# DebugPowerSupplyBoard.net
KiCad netlist of a schematic drawn in EAGLE
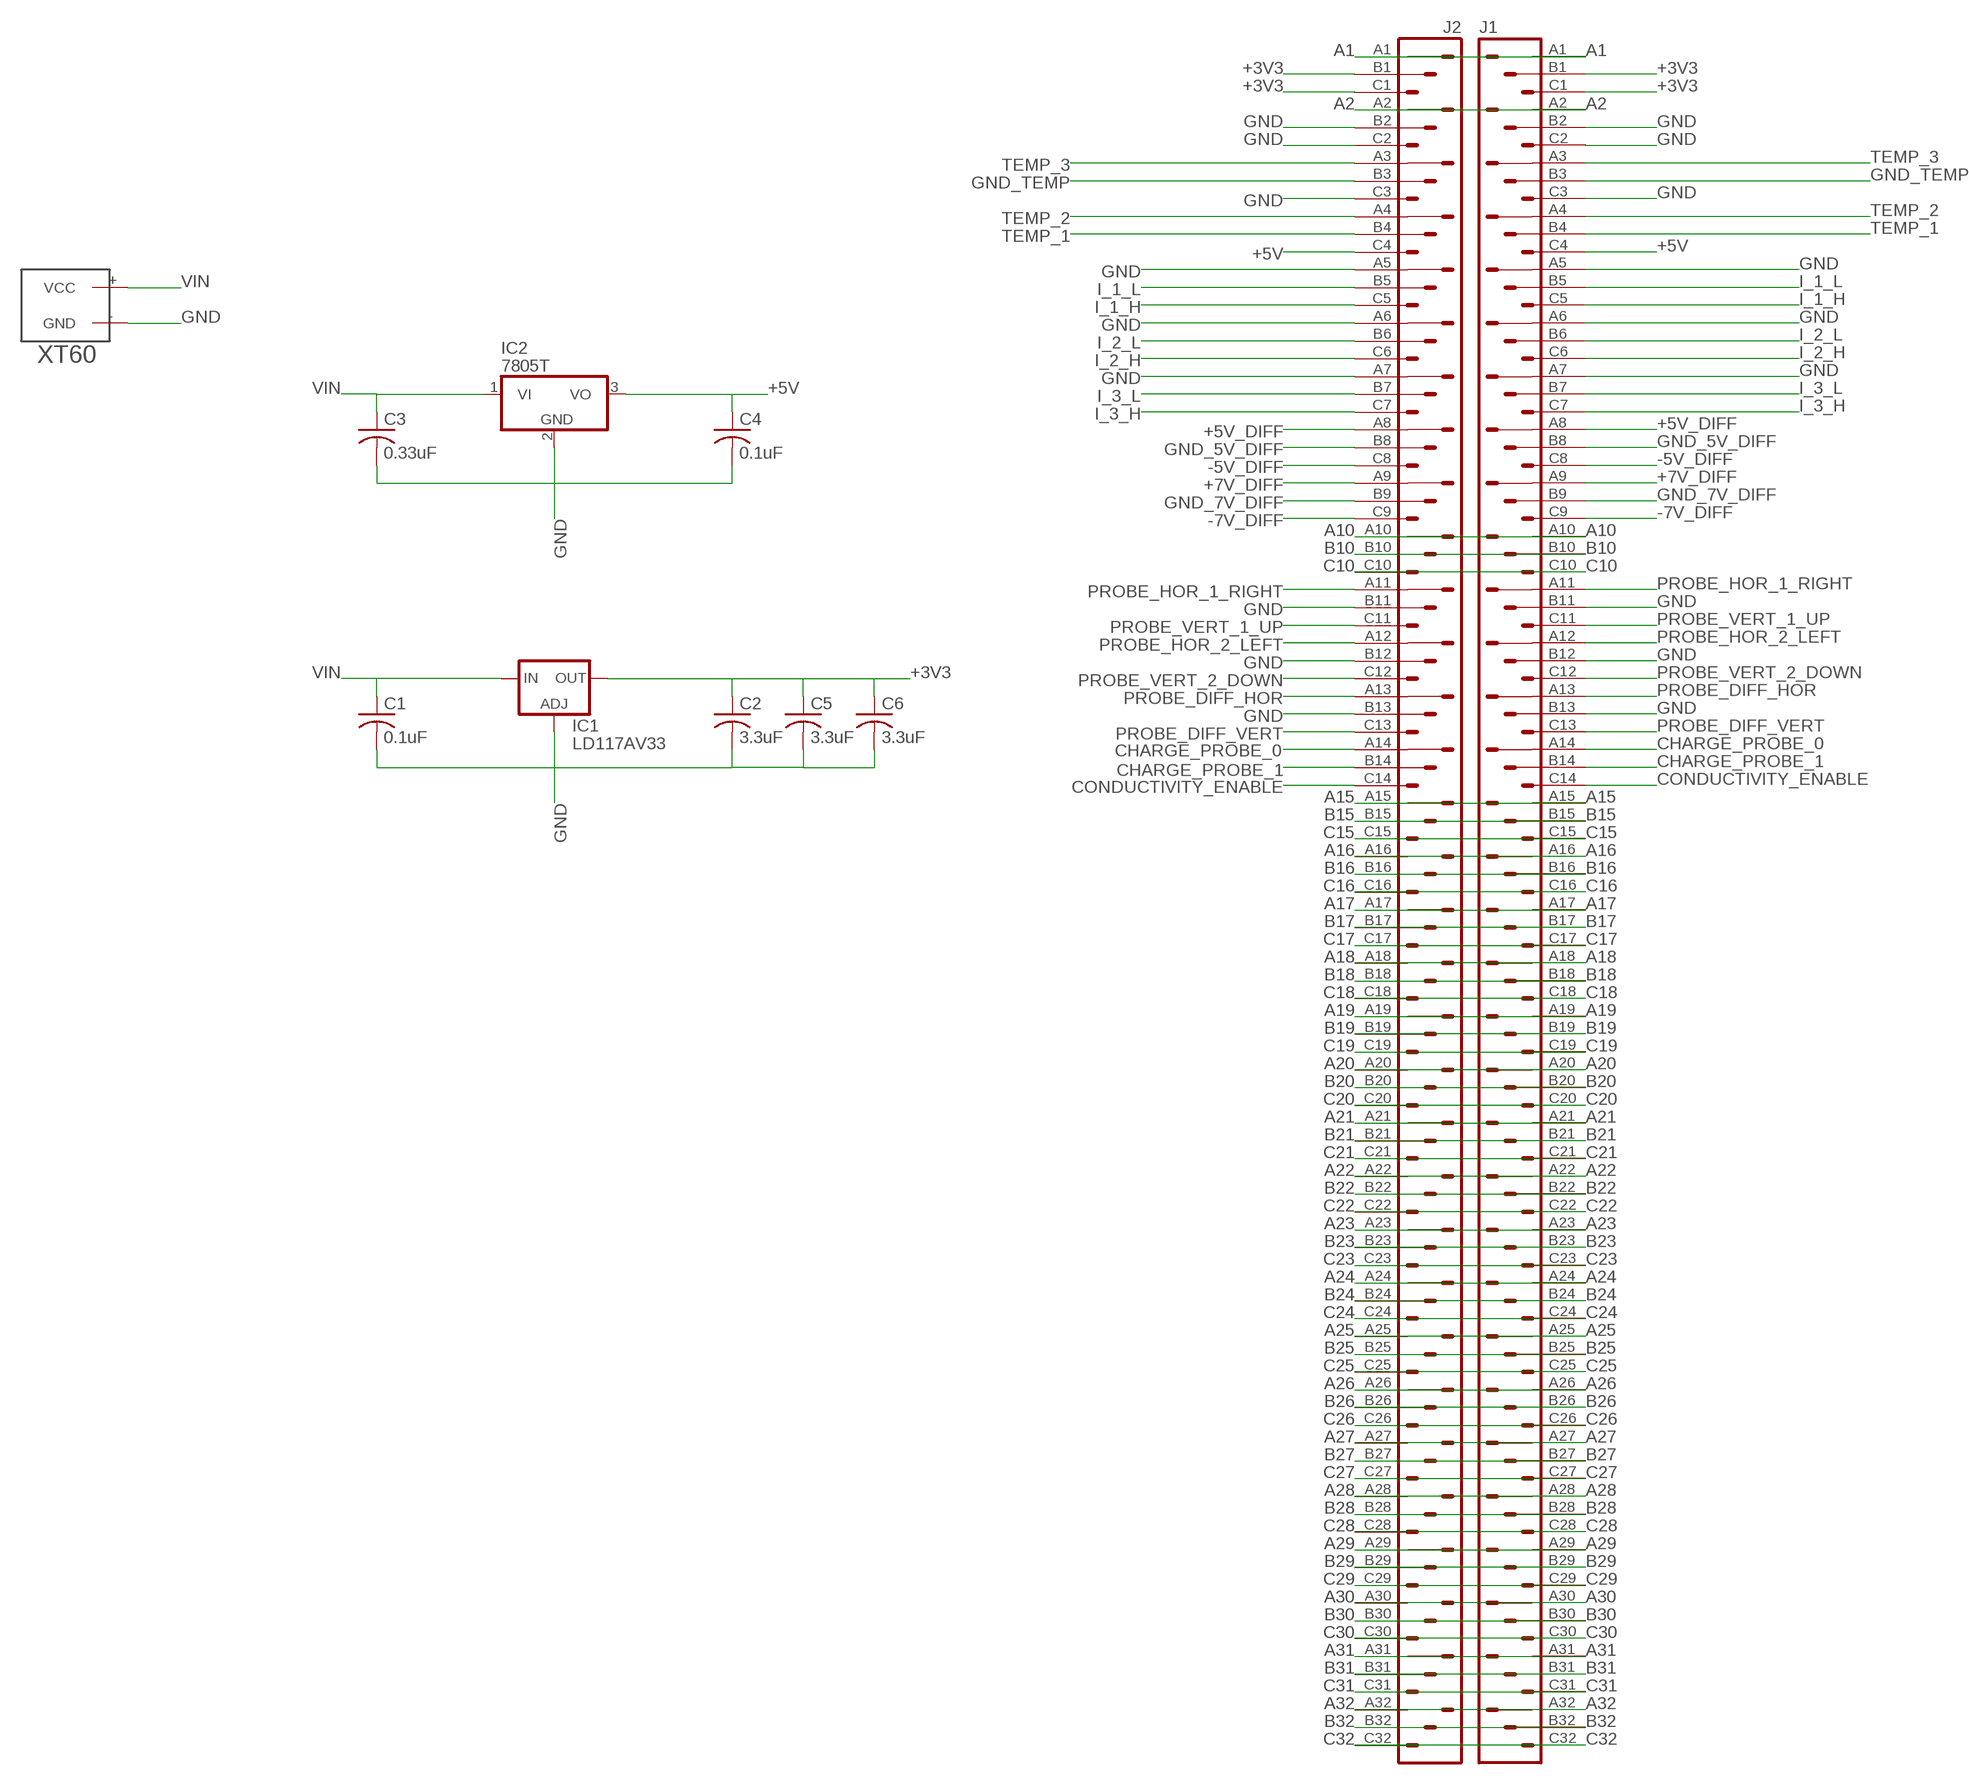
[diagram p0: schematic, sheet 1]

(export (version "E")
  (design (tool "Eeschema 10.0.6"))
  (components
    (comp (ref "C1")
      (value "0.1uF")
      (footprint "eagle-import:C050-025X075")
      (libsource (lib "eagle-import") (part "C-US050-025X075"))
    )
    (comp (ref "C2")
      (value "3.3uF")
      (footprint "eagle-import:C050-055X075")
      (libsource (lib "eagle-import") (part "C-US050-055X075"))
    )
    (comp (ref "C3")
      (value "0.33uF")
      (footprint "eagle-import:C050-035X075")
      (libsource (lib "eagle-import") (part "C-US050-035X075"))
    )
    (comp (ref "C4")
      (value "0.1uF")
      (footprint "eagle-import:C050-025X075")
      (libsource (lib "eagle-import") (part "C-US050-025X075"))
    )
    (comp (ref "C5")
      (value "3.3uF")
      (footprint "eagle-import:C050-055X075")
      (libsource (lib "eagle-import") (part "C-US050-055X075"))
    )
    (comp (ref "C6")
      (value "3.3uF")
      (footprint "eagle-import:C050-055X075")
      (libsource (lib "eagle-import") (part "C-US050-055X075"))
    )
    (comp (ref "IC1")
      (value "LD117AV33")
      (footprint "eagle-import:TO220L1")
      (libsource (lib "eagle-import") (part "LD117A?V33"))
    )
    (comp (ref "IC2")
      (value "7805T")
      (footprint "eagle-import:TO220H")
      (libsource (lib "eagle-import") (part "78T05"))
    )
    (comp (ref "J1")
      (value "VG96KB")
      (footprint "eagle-import:VG96KB")
      (libsource (lib "eagle-import") (part "CustomEuroCard_VG96KB"))
    )
    (comp (ref "J2")
      (value "VG96KB")
      (footprint "eagle-import:VG96KB")
      (libsource (lib "eagle-import") (part "VG96KB"))
    )
    (comp (ref "U$6")
      (value "XT60")
      (footprint "eagle-import:XT60")
      (libsource (lib "eagle-import") (part "XT60"))
    )
  )
  (nets
    (net (code "1") (name "/+3V3") (class "Default")
      (node (ref "C2") (pin "1") (pinfunction "1_1") (pintype "passive"))
      (node (ref "C5") (pin "1") (pinfunction "1_1") (pintype "passive"))
      (node (ref "C6") (pin "1") (pinfunction "1_1") (pintype "passive"))
      (node (ref "IC1") (pin "2") (pinfunction "OUT_2") (pintype "passive"))
      (node (ref "J1") (pin "B1") (pinfunction "B1_B1") (pintype "passive"))
      (node (ref "J1") (pin "C1") (pinfunction "C1_C1") (pintype "passive"))
      (node (ref "J2") (pin "B1") (pinfunction "B1_B1") (pintype "passive"))
      (node (ref "J2") (pin "C1") (pinfunction "C1_C1") (pintype "passive"))
    )
    (net (code "2") (name "/+5V") (class "Default")
      (node (ref "C4") (pin "1") (pinfunction "1_1") (pintype "passive"))
      (node (ref "IC2") (pin "3") (pinfunction "VO_3") (pintype "passive"))
      (node (ref "J1") (pin "C4") (pinfunction "C4_C4") (pintype "passive"))
      (node (ref "J2") (pin "C4") (pinfunction "C4_C4") (pintype "passive"))
    )
    (net (code "3") (name "/+5V_DIFF") (class "Default")
      (node (ref "J1") (pin "A8") (pinfunction "A8_A8") (pintype "passive"))
      (node (ref "J2") (pin "A8") (pinfunction "A8_A8") (pintype "passive"))
    )
    (net (code "4") (name "/+7V_DIFF") (class "Default")
      (node (ref "J1") (pin "A9") (pinfunction "A9_A9") (pintype "passive"))
      (node (ref "J2") (pin "A9") (pinfunction "A9_A9") (pintype "passive"))
    )
    (net (code "5") (name "/-5V_DIFF") (class "Default")
      (node (ref "J1") (pin "C8") (pinfunction "C8_C8") (pintype "passive"))
      (node (ref "J2") (pin "C8") (pinfunction "C8_C8") (pintype "passive"))
    )
    (net (code "6") (name "/-7V_DIFF") (class "Default")
      (node (ref "J1") (pin "C9") (pinfunction "C9_C9") (pintype "passive"))
      (node (ref "J2") (pin "C9") (pinfunction "C9_C9") (pintype "passive"))
    )
    (net (code "7") (name "/A1") (class "Default")
      (node (ref "J1") (pin "A1") (pinfunction "A1_A1") (pintype "passive"))
      (node (ref "J2") (pin "A1") (pinfunction "A1_A1") (pintype "passive"))
    )
    (net (code "8") (name "/A2") (class "Default")
      (node (ref "J1") (pin "A2") (pinfunction "A2_A2") (pintype "passive"))
      (node (ref "J2") (pin "A2") (pinfunction "A2_A2") (pintype "passive"))
    )
    (net (code "9") (name "/A10") (class "Default")
      (node (ref "J1") (pin "A10") (pinfunction "A10_A10") (pintype "passive"))
      (node (ref "J2") (pin "A10") (pinfunction "A10_A10") (pintype "passive"))
    )
    (net (code "10") (name "/A15") (class "Default")
      (node (ref "J1") (pin "A15") (pinfunction "A15_A15") (pintype "passive"))
      (node (ref "J2") (pin "A15") (pinfunction "A15_A15") (pintype "passive"))
    )
    (net (code "11") (name "/A16") (class "Default")
      (node (ref "J1") (pin "A16") (pinfunction "A16_A16") (pintype "passive"))
      (node (ref "J2") (pin "A16") (pinfunction "A16_A16") (pintype "passive"))
    )
    (net (code "12") (name "/A17") (class "Default")
      (node (ref "J1") (pin "A17") (pinfunction "A17_A17") (pintype "passive"))
      (node (ref "J2") (pin "A17") (pinfunction "A17_A17") (pintype "passive"))
    )
    (net (code "13") (name "/A18") (class "Default")
      (node (ref "J1") (pin "A18") (pinfunction "A18_A18") (pintype "passive"))
      (node (ref "J2") (pin "A18") (pinfunction "A18_A18") (pintype "passive"))
    )
    (net (code "14") (name "/A19") (class "Default")
      (node (ref "J1") (pin "A19") (pinfunction "A19_A19") (pintype "passive"))
      (node (ref "J2") (pin "A19") (pinfunction "A19_A19") (pintype "passive"))
    )
    (net (code "15") (name "/A20") (class "Default")
      (node (ref "J1") (pin "A20") (pinfunction "A20_A20") (pintype "passive"))
      (node (ref "J2") (pin "A20") (pinfunction "A20_A20") (pintype "passive"))
    )
    (net (code "16") (name "/A21") (class "Default")
      (node (ref "J1") (pin "A21") (pinfunction "A21_A21") (pintype "passive"))
      (node (ref "J2") (pin "A21") (pinfunction "A21_A21") (pintype "passive"))
    )
    (net (code "17") (name "/A22") (class "Default")
      (node (ref "J1") (pin "A22") (pinfunction "A22_A22") (pintype "passive"))
      (node (ref "J2") (pin "A22") (pinfunction "A22_A22") (pintype "passive"))
    )
    (net (code "18") (name "/A23") (class "Default")
      (node (ref "J1") (pin "A23") (pinfunction "A23_A23") (pintype "passive"))
      (node (ref "J2") (pin "A23") (pinfunction "A23_A23") (pintype "passive"))
    )
    (net (code "19") (name "/A24") (class "Default")
      (node (ref "J1") (pin "A24") (pinfunction "A24_A24") (pintype "passive"))
      (node (ref "J2") (pin "A24") (pinfunction "A24_A24") (pintype "passive"))
    )
    (net (code "20") (name "/A25") (class "Default")
      (node (ref "J1") (pin "A25") (pinfunction "A25_A25") (pintype "passive"))
      (node (ref "J2") (pin "A25") (pinfunction "A25_A25") (pintype "passive"))
    )
    (net (code "21") (name "/A26") (class "Default")
      (node (ref "J1") (pin "A26") (pinfunction "A26_A26") (pintype "passive"))
      (node (ref "J2") (pin "A26") (pinfunction "A26_A26") (pintype "passive"))
    )
    (net (code "22") (name "/A27") (class "Default")
      (node (ref "J1") (pin "A27") (pinfunction "A27_A27") (pintype "passive"))
      (node (ref "J2") (pin "A27") (pinfunction "A27_A27") (pintype "passive"))
    )
    (net (code "23") (name "/A28") (class "Default")
      (node (ref "J1") (pin "A28") (pinfunction "A28_A28") (pintype "passive"))
      (node (ref "J2") (pin "A28") (pinfunction "A28_A28") (pintype "passive"))
    )
    (net (code "24") (name "/A29") (class "Default")
      (node (ref "J1") (pin "A29") (pinfunction "A29_A29") (pintype "passive"))
      (node (ref "J2") (pin "A29") (pinfunction "A29_A29") (pintype "passive"))
    )
    (net (code "25") (name "/A30") (class "Default")
      (node (ref "J1") (pin "A30") (pinfunction "A30_A30") (pintype "passive"))
      (node (ref "J2") (pin "A30") (pinfunction "A30_A30") (pintype "passive"))
    )
    (net (code "26") (name "/A31") (class "Default")
      (node (ref "J1") (pin "A31") (pinfunction "A31_A31") (pintype "passive"))
      (node (ref "J2") (pin "A31") (pinfunction "A31_A31") (pintype "passive"))
    )
    (net (code "27") (name "/A32") (class "Default")
      (node (ref "J1") (pin "A32") (pinfunction "A32_A32") (pintype "passive"))
      (node (ref "J2") (pin "A32") (pinfunction "A32_A32") (pintype "passive"))
    )
    (net (code "28") (name "/B10") (class "Default")
      (node (ref "J1") (pin "B10") (pinfunction "B10_B10") (pintype "passive"))
      (node (ref "J2") (pin "B10") (pinfunction "B10_B10") (pintype "passive"))
    )
    (net (code "29") (name "/B15") (class "Default")
      (node (ref "J1") (pin "B15") (pinfunction "B15_B15") (pintype "passive"))
      (node (ref "J2") (pin "B15") (pinfunction "B15_B15") (pintype "passive"))
    )
    (net (code "30") (name "/B16") (class "Default")
      (node (ref "J1") (pin "B16") (pinfunction "B16_B16") (pintype "passive"))
      (node (ref "J2") (pin "B16") (pinfunction "B16_B16") (pintype "passive"))
    )
    (net (code "31") (name "/B17") (class "Default")
      (node (ref "J1") (pin "B17") (pinfunction "B17_B17") (pintype "passive"))
      (node (ref "J2") (pin "B17") (pinfunction "B17_B17") (pintype "passive"))
    )
    (net (code "32") (name "/B18") (class "Default")
      (node (ref "J1") (pin "B18") (pinfunction "B18_B18") (pintype "passive"))
      (node (ref "J2") (pin "B18") (pinfunction "B18_B18") (pintype "passive"))
    )
    (net (code "33") (name "/B19") (class "Default")
      (node (ref "J1") (pin "B19") (pinfunction "B19_B19") (pintype "passive"))
      (node (ref "J2") (pin "B19") (pinfunction "B19_B19") (pintype "passive"))
    )
    (net (code "34") (name "/B20") (class "Default")
      (node (ref "J1") (pin "B20") (pinfunction "B20_B20") (pintype "passive"))
      (node (ref "J2") (pin "B20") (pinfunction "B20_B20") (pintype "passive"))
    )
    (net (code "35") (name "/B21") (class "Default")
      (node (ref "J1") (pin "B21") (pinfunction "B21_B21") (pintype "passive"))
      (node (ref "J2") (pin "B21") (pinfunction "B21_B21") (pintype "passive"))
    )
    (net (code "36") (name "/B22") (class "Default")
      (node (ref "J1") (pin "B22") (pinfunction "B22_B22") (pintype "passive"))
      (node (ref "J2") (pin "B22") (pinfunction "B22_B22") (pintype "passive"))
    )
    (net (code "37") (name "/B23") (class "Default")
      (node (ref "J1") (pin "B23") (pinfunction "B23_B23") (pintype "passive"))
      (node (ref "J2") (pin "B23") (pinfunction "B23_B23") (pintype "passive"))
    )
    (net (code "38") (name "/B24") (class "Default")
      (node (ref "J1") (pin "B24") (pinfunction "B24_B24") (pintype "passive"))
      (node (ref "J2") (pin "B24") (pinfunction "B24_B24") (pintype "passive"))
    )
    (net (code "39") (name "/B25") (class "Default")
      (node (ref "J1") (pin "B25") (pinfunction "B25_B25") (pintype "passive"))
      (node (ref "J2") (pin "B25") (pinfunction "B25_B25") (pintype "passive"))
    )
    (net (code "40") (name "/B26") (class "Default")
      (node (ref "J1") (pin "B26") (pinfunction "B26_B26") (pintype "passive"))
      (node (ref "J2") (pin "B26") (pinfunction "B26_B26") (pintype "passive"))
    )
    (net (code "41") (name "/B27") (class "Default")
      (node (ref "J1") (pin "B27") (pinfunction "B27_B27") (pintype "passive"))
      (node (ref "J2") (pin "B27") (pinfunction "B27_B27") (pintype "passive"))
    )
    (net (code "42") (name "/B28") (class "Default")
      (node (ref "J1") (pin "B28") (pinfunction "B28_B28") (pintype "passive"))
      (node (ref "J2") (pin "B28") (pinfunction "B28_B28") (pintype "passive"))
    )
    (net (code "43") (name "/B29") (class "Default")
      (node (ref "J1") (pin "B29") (pinfunction "B29_B29") (pintype "passive"))
      (node (ref "J2") (pin "B29") (pinfunction "B29_B29") (pintype "passive"))
    )
    (net (code "44") (name "/B30") (class "Default")
      (node (ref "J1") (pin "B30") (pinfunction "B30_B30") (pintype "passive"))
      (node (ref "J2") (pin "B30") (pinfunction "B30_B30") (pintype "passive"))
    )
    (net (code "45") (name "/B31") (class "Default")
      (node (ref "J1") (pin "B31") (pinfunction "B31_B31") (pintype "passive"))
      (node (ref "J2") (pin "B31") (pinfunction "B31_B31") (pintype "passive"))
    )
    (net (code "46") (name "/B32") (class "Default")
      (node (ref "J1") (pin "B32") (pinfunction "B32_B32") (pintype "passive"))
      (node (ref "J2") (pin "B32") (pinfunction "B32_B32") (pintype "passive"))
    )
    (net (code "47") (name "/C10") (class "Default")
      (node (ref "J1") (pin "C10") (pinfunction "C10_C10") (pintype "passive"))
      (node (ref "J2") (pin "C10") (pinfunction "C10_C10") (pintype "passive"))
    )
    (net (code "48") (name "/C15") (class "Default")
      (node (ref "J1") (pin "C15") (pinfunction "C15_C15") (pintype "passive"))
      (node (ref "J2") (pin "C15") (pinfunction "C15_C15") (pintype "passive"))
    )
    (net (code "49") (name "/C16") (class "Default")
      (node (ref "J1") (pin "C16") (pinfunction "C16_C16") (pintype "passive"))
      (node (ref "J2") (pin "C16") (pinfunction "C16_C16") (pintype "passive"))
    )
    (net (code "50") (name "/C17") (class "Default")
      (node (ref "J1") (pin "C17") (pinfunction "C17_C17") (pintype "passive"))
      (node (ref "J2") (pin "C17") (pinfunction "C17_C17") (pintype "passive"))
    )
    (net (code "51") (name "/C18") (class "Default")
      (node (ref "J1") (pin "C18") (pinfunction "C18_C18") (pintype "passive"))
      (node (ref "J2") (pin "C18") (pinfunction "C18_C18") (pintype "passive"))
    )
    (net (code "52") (name "/C19") (class "Default")
      (node (ref "J1") (pin "C19") (pinfunction "C19_C19") (pintype "passive"))
      (node (ref "J2") (pin "C19") (pinfunction "C19_C19") (pintype "passive"))
    )
    (net (code "53") (name "/C20") (class "Default")
      (node (ref "J1") (pin "C20") (pinfunction "C20_C20") (pintype "passive"))
      (node (ref "J2") (pin "C20") (pinfunction "C20_C20") (pintype "passive"))
    )
    (net (code "54") (name "/C21") (class "Default")
      (node (ref "J1") (pin "C21") (pinfunction "C21_C21") (pintype "passive"))
      (node (ref "J2") (pin "C21") (pinfunction "C21_C21") (pintype "passive"))
    )
    (net (code "55") (name "/C22") (class "Default")
      (node (ref "J1") (pin "C22") (pinfunction "C22_C22") (pintype "passive"))
      (node (ref "J2") (pin "C22") (pinfunction "C22_C22") (pintype "passive"))
    )
    (net (code "56") (name "/C23") (class "Default")
      (node (ref "J1") (pin "C23") (pinfunction "C23_C23") (pintype "passive"))
      (node (ref "J2") (pin "C23") (pinfunction "C23_C23") (pintype "passive"))
    )
    (net (code "57") (name "/C24") (class "Default")
      (node (ref "J1") (pin "C24") (pinfunction "C24_C24") (pintype "passive"))
      (node (ref "J2") (pin "C24") (pinfunction "C24_C24") (pintype "passive"))
    )
    (net (code "58") (name "/C25") (class "Default")
      (node (ref "J1") (pin "C25") (pinfunction "C25_C25") (pintype "passive"))
      (node (ref "J2") (pin "C25") (pinfunction "C25_C25") (pintype "passive"))
    )
    (net (code "59") (name "/C26") (class "Default")
      (node (ref "J1") (pin "C26") (pinfunction "C26_C26") (pintype "passive"))
      (node (ref "J2") (pin "C26") (pinfunction "C26_C26") (pintype "passive"))
    )
    (net (code "60") (name "/C27") (class "Default")
      (node (ref "J1") (pin "C27") (pinfunction "C27_C27") (pintype "passive"))
      (node (ref "J2") (pin "C27") (pinfunction "C27_C27") (pintype "passive"))
    )
    (net (code "61") (name "/C28") (class "Default")
      (node (ref "J1") (pin "C28") (pinfunction "C28_C28") (pintype "passive"))
      (node (ref "J2") (pin "C28") (pinfunction "C28_C28") (pintype "passive"))
    )
    (net (code "62") (name "/C29") (class "Default")
      (node (ref "J1") (pin "C29") (pinfunction "C29_C29") (pintype "passive"))
      (node (ref "J2") (pin "C29") (pinfunction "C29_C29") (pintype "passive"))
    )
    (net (code "63") (name "/C30") (class "Default")
      (node (ref "J1") (pin "C30") (pinfunction "C30_C30") (pintype "passive"))
      (node (ref "J2") (pin "C30") (pinfunction "C30_C30") (pintype "passive"))
    )
    (net (code "64") (name "/C31") (class "Default")
      (node (ref "J1") (pin "C31") (pinfunction "C31_C31") (pintype "passive"))
      (node (ref "J2") (pin "C31") (pinfunction "C31_C31") (pintype "passive"))
    )
    (net (code "65") (name "/C32") (class "Default")
      (node (ref "J1") (pin "C32") (pinfunction "C32_C32") (pintype "passive"))
      (node (ref "J2") (pin "C32") (pinfunction "C32_C32") (pintype "passive"))
    )
    (net (code "66") (name "/CHARGE_PROBE_0") (class "Default")
      (node (ref "J1") (pin "A14") (pinfunction "A14_A14") (pintype "passive"))
      (node (ref "J2") (pin "A14") (pinfunction "A14_A14") (pintype "passive"))
    )
    (net (code "67") (name "/CHARGE_PROBE_1") (class "Default")
      (node (ref "J1") (pin "B14") (pinfunction "B14_B14") (pintype "passive"))
      (node (ref "J2") (pin "B14") (pinfunction "B14_B14") (pintype "passive"))
    )
    (net (code "68") (name "/CONDUCTIVITY_ENABLE") (class "Default")
      (node (ref "J1") (pin "C14") (pinfunction "C14_C14") (pintype "passive"))
      (node (ref "J2") (pin "C14") (pinfunction "C14_C14") (pintype "passive"))
    )
    (net (code "69") (name "/GND") (class "Default")
      (node (ref "C1") (pin "2") (pinfunction "2_2") (pintype "passive"))
      (node (ref "C2") (pin "2") (pinfunction "2_2") (pintype "passive"))
      (node (ref "C3") (pin "2") (pinfunction "2_2") (pintype "passive"))
      (node (ref "C4") (pin "2") (pinfunction "2_2") (pintype "passive"))
      (node (ref "C5") (pin "2") (pinfunction "2_2") (pintype "passive"))
      (node (ref "C6") (pin "2") (pinfunction "2_2") (pintype "passive"))
      (node (ref "IC1") (pin "1") (pinfunction "ADJ_1") (pintype "input"))
      (node (ref "IC2") (pin "2") (pinfunction "GND_2") (pintype "passive"))
      (node (ref "J1") (pin "A5") (pinfunction "A5_A5") (pintype "passive"))
      (node (ref "J1") (pin "A6") (pinfunction "A6_A6") (pintype "passive"))
      (node (ref "J1") (pin "A7") (pinfunction "A7_A7") (pintype "passive"))
      (node (ref "J1") (pin "B11") (pinfunction "B11_B11") (pintype "passive"))
      (node (ref "J1") (pin "B12") (pinfunction "B12_B12") (pintype "passive"))
      (node (ref "J1") (pin "B13") (pinfunction "B13_B13") (pintype "passive"))
      (node (ref "J1") (pin "B2") (pinfunction "B2_B2") (pintype "passive"))
      (node (ref "J1") (pin "C2") (pinfunction "C2_C2") (pintype "passive"))
      (node (ref "J1") (pin "C3") (pinfunction "C3_C3") (pintype "passive"))
      (node (ref "J2") (pin "A5") (pinfunction "A5_A5") (pintype "passive"))
      (node (ref "J2") (pin "A6") (pinfunction "A6_A6") (pintype "passive"))
      (node (ref "J2") (pin "A7") (pinfunction "A7_A7") (pintype "passive"))
      (node (ref "J2") (pin "B11") (pinfunction "B11_B11") (pintype "passive"))
      (node (ref "J2") (pin "B12") (pinfunction "B12_B12") (pintype "passive"))
      (node (ref "J2") (pin "B13") (pinfunction "B13_B13") (pintype "passive"))
      (node (ref "J2") (pin "B2") (pinfunction "B2_B2") (pintype "passive"))
      (node (ref "J2") (pin "C2") (pinfunction "C2_C2") (pintype "passive"))
      (node (ref "J2") (pin "C3") (pinfunction "C3_C3") (pintype "passive"))
      (node (ref "U$6") (pin "-") (pinfunction "GND_-") (pintype "bidirectional"))
    )
    (net (code "70") (name "/GND_5V_DIFF") (class "Default")
      (node (ref "J1") (pin "B8") (pinfunction "B8_B8") (pintype "passive"))
      (node (ref "J2") (pin "B8") (pinfunction "B8_B8") (pintype "passive"))
    )
    (net (code "71") (name "/GND_7V_DIFF") (class "Default")
      (node (ref "J1") (pin "B9") (pinfunction "B9_B9") (pintype "passive"))
      (node (ref "J2") (pin "B9") (pinfunction "B9_B9") (pintype "passive"))
    )
    (net (code "72") (name "/GND_TEMP") (class "Default")
      (node (ref "J1") (pin "B3") (pinfunction "B3_B3") (pintype "passive"))
      (node (ref "J2") (pin "B3") (pinfunction "B3_B3") (pintype "passive"))
    )
    (net (code "73") (name "/I_1_H") (class "Default")
      (node (ref "J1") (pin "C5") (pinfunction "C5_C5") (pintype "passive"))
      (node (ref "J2") (pin "C5") (pinfunction "C5_C5") (pintype "passive"))
    )
    (net (code "74") (name "/I_1_L") (class "Default")
      (node (ref "J1") (pin "B5") (pinfunction "B5_B5") (pintype "passive"))
      (node (ref "J2") (pin "B5") (pinfunction "B5_B5") (pintype "passive"))
    )
    (net (code "75") (name "/I_2_H") (class "Default")
      (node (ref "J1") (pin "C6") (pinfunction "C6_C6") (pintype "passive"))
      (node (ref "J2") (pin "C6") (pinfunction "C6_C6") (pintype "passive"))
    )
    (net (code "76") (name "/I_2_L") (class "Default")
      (node (ref "J1") (pin "B6") (pinfunction "B6_B6") (pintype "passive"))
      (node (ref "J2") (pin "B6") (pinfunction "B6_B6") (pintype "passive"))
    )
    (net (code "77") (name "/I_3_H") (class "Default")
      (node (ref "J1") (pin "C7") (pinfunction "C7_C7") (pintype "passive"))
      (node (ref "J2") (pin "C7") (pinfunction "C7_C7") (pintype "passive"))
    )
    (net (code "78") (name "/I_3_L") (class "Default")
      (node (ref "J1") (pin "B7") (pinfunction "B7_B7") (pintype "passive"))
      (node (ref "J2") (pin "B7") (pinfunction "B7_B7") (pintype "passive"))
    )
    (net (code "79") (name "/PROBE_DIFF_HOR") (class "Default")
      (node (ref "J1") (pin "A13") (pinfunction "A13_A13") (pintype "passive"))
      (node (ref "J2") (pin "A13") (pinfunction "A13_A13") (pintype "passive"))
    )
    (net (code "80") (name "/PROBE_DIFF_VERT") (class "Default")
      (node (ref "J1") (pin "C13") (pinfunction "C13_C13") (pintype "passive"))
      (node (ref "J2") (pin "C13") (pinfunction "C13_C13") (pintype "passive"))
    )
    (net (code "81") (name "/PROBE_HOR_1_RIGHT") (class "Default")
      (node (ref "J1") (pin "A11") (pinfunction "A11_A11") (pintype "passive"))
      (node (ref "J2") (pin "A11") (pinfunction "A11_A11") (pintype "passive"))
    )
    (net (code "82") (name "/PROBE_HOR_2_LEFT") (class "Default")
      (node (ref "J1") (pin "A12") (pinfunction "A12_A12") (pintype "passive"))
      (node (ref "J2") (pin "A12") (pinfunction "A12_A12") (pintype "passive"))
    )
    (net (code "83") (name "/PROBE_VERT_1_UP") (class "Default")
      (node (ref "J1") (pin "C11") (pinfunction "C11_C11") (pintype "passive"))
      (node (ref "J2") (pin "C11") (pinfunction "C11_C11") (pintype "passive"))
    )
    (net (code "84") (name "/PROBE_VERT_2_DOWN") (class "Default")
      (node (ref "J1") (pin "C12") (pinfunction "C12_C12") (pintype "passive"))
      (node (ref "J2") (pin "C12") (pinfunction "C12_C12") (pintype "passive"))
    )
    (net (code "85") (name "/TEMP_1") (class "Default")
      (node (ref "J1") (pin "B4") (pinfunction "B4_B4") (pintype "passive"))
      (node (ref "J2") (pin "B4") (pinfunction "B4_B4") (pintype "passive"))
    )
    (net (code "86") (name "/TEMP_2") (class "Default")
      (node (ref "J1") (pin "A4") (pinfunction "A4_A4") (pintype "passive"))
      (node (ref "J2") (pin "A4") (pinfunction "A4_A4") (pintype "passive"))
    )
    (net (code "87") (name "/TEMP_3") (class "Default")
      (node (ref "J1") (pin "A3") (pinfunction "A3_A3") (pintype "passive"))
      (node (ref "J2") (pin "A3") (pinfunction "A3_A3") (pintype "passive"))
    )
    (net (code "88") (name "/VIN") (class "Default")
      (node (ref "C1") (pin "1") (pinfunction "1_1") (pintype "passive"))
      (node (ref "C3") (pin "1") (pinfunction "1_1") (pintype "passive"))
      (node (ref "IC1") (pin "3") (pinfunction "IN_3") (pintype "input"))
      (node (ref "IC2") (pin "1") (pinfunction "VI_1") (pintype "input"))
      (node (ref "U$6") (pin "+") (pinfunction "VCC_+") (pintype "bidirectional"))
    )
  )
)
